# Nakuja_esp_lora_gps_sd.net
KiCad netlist of a schematic drawn in EasyEDA
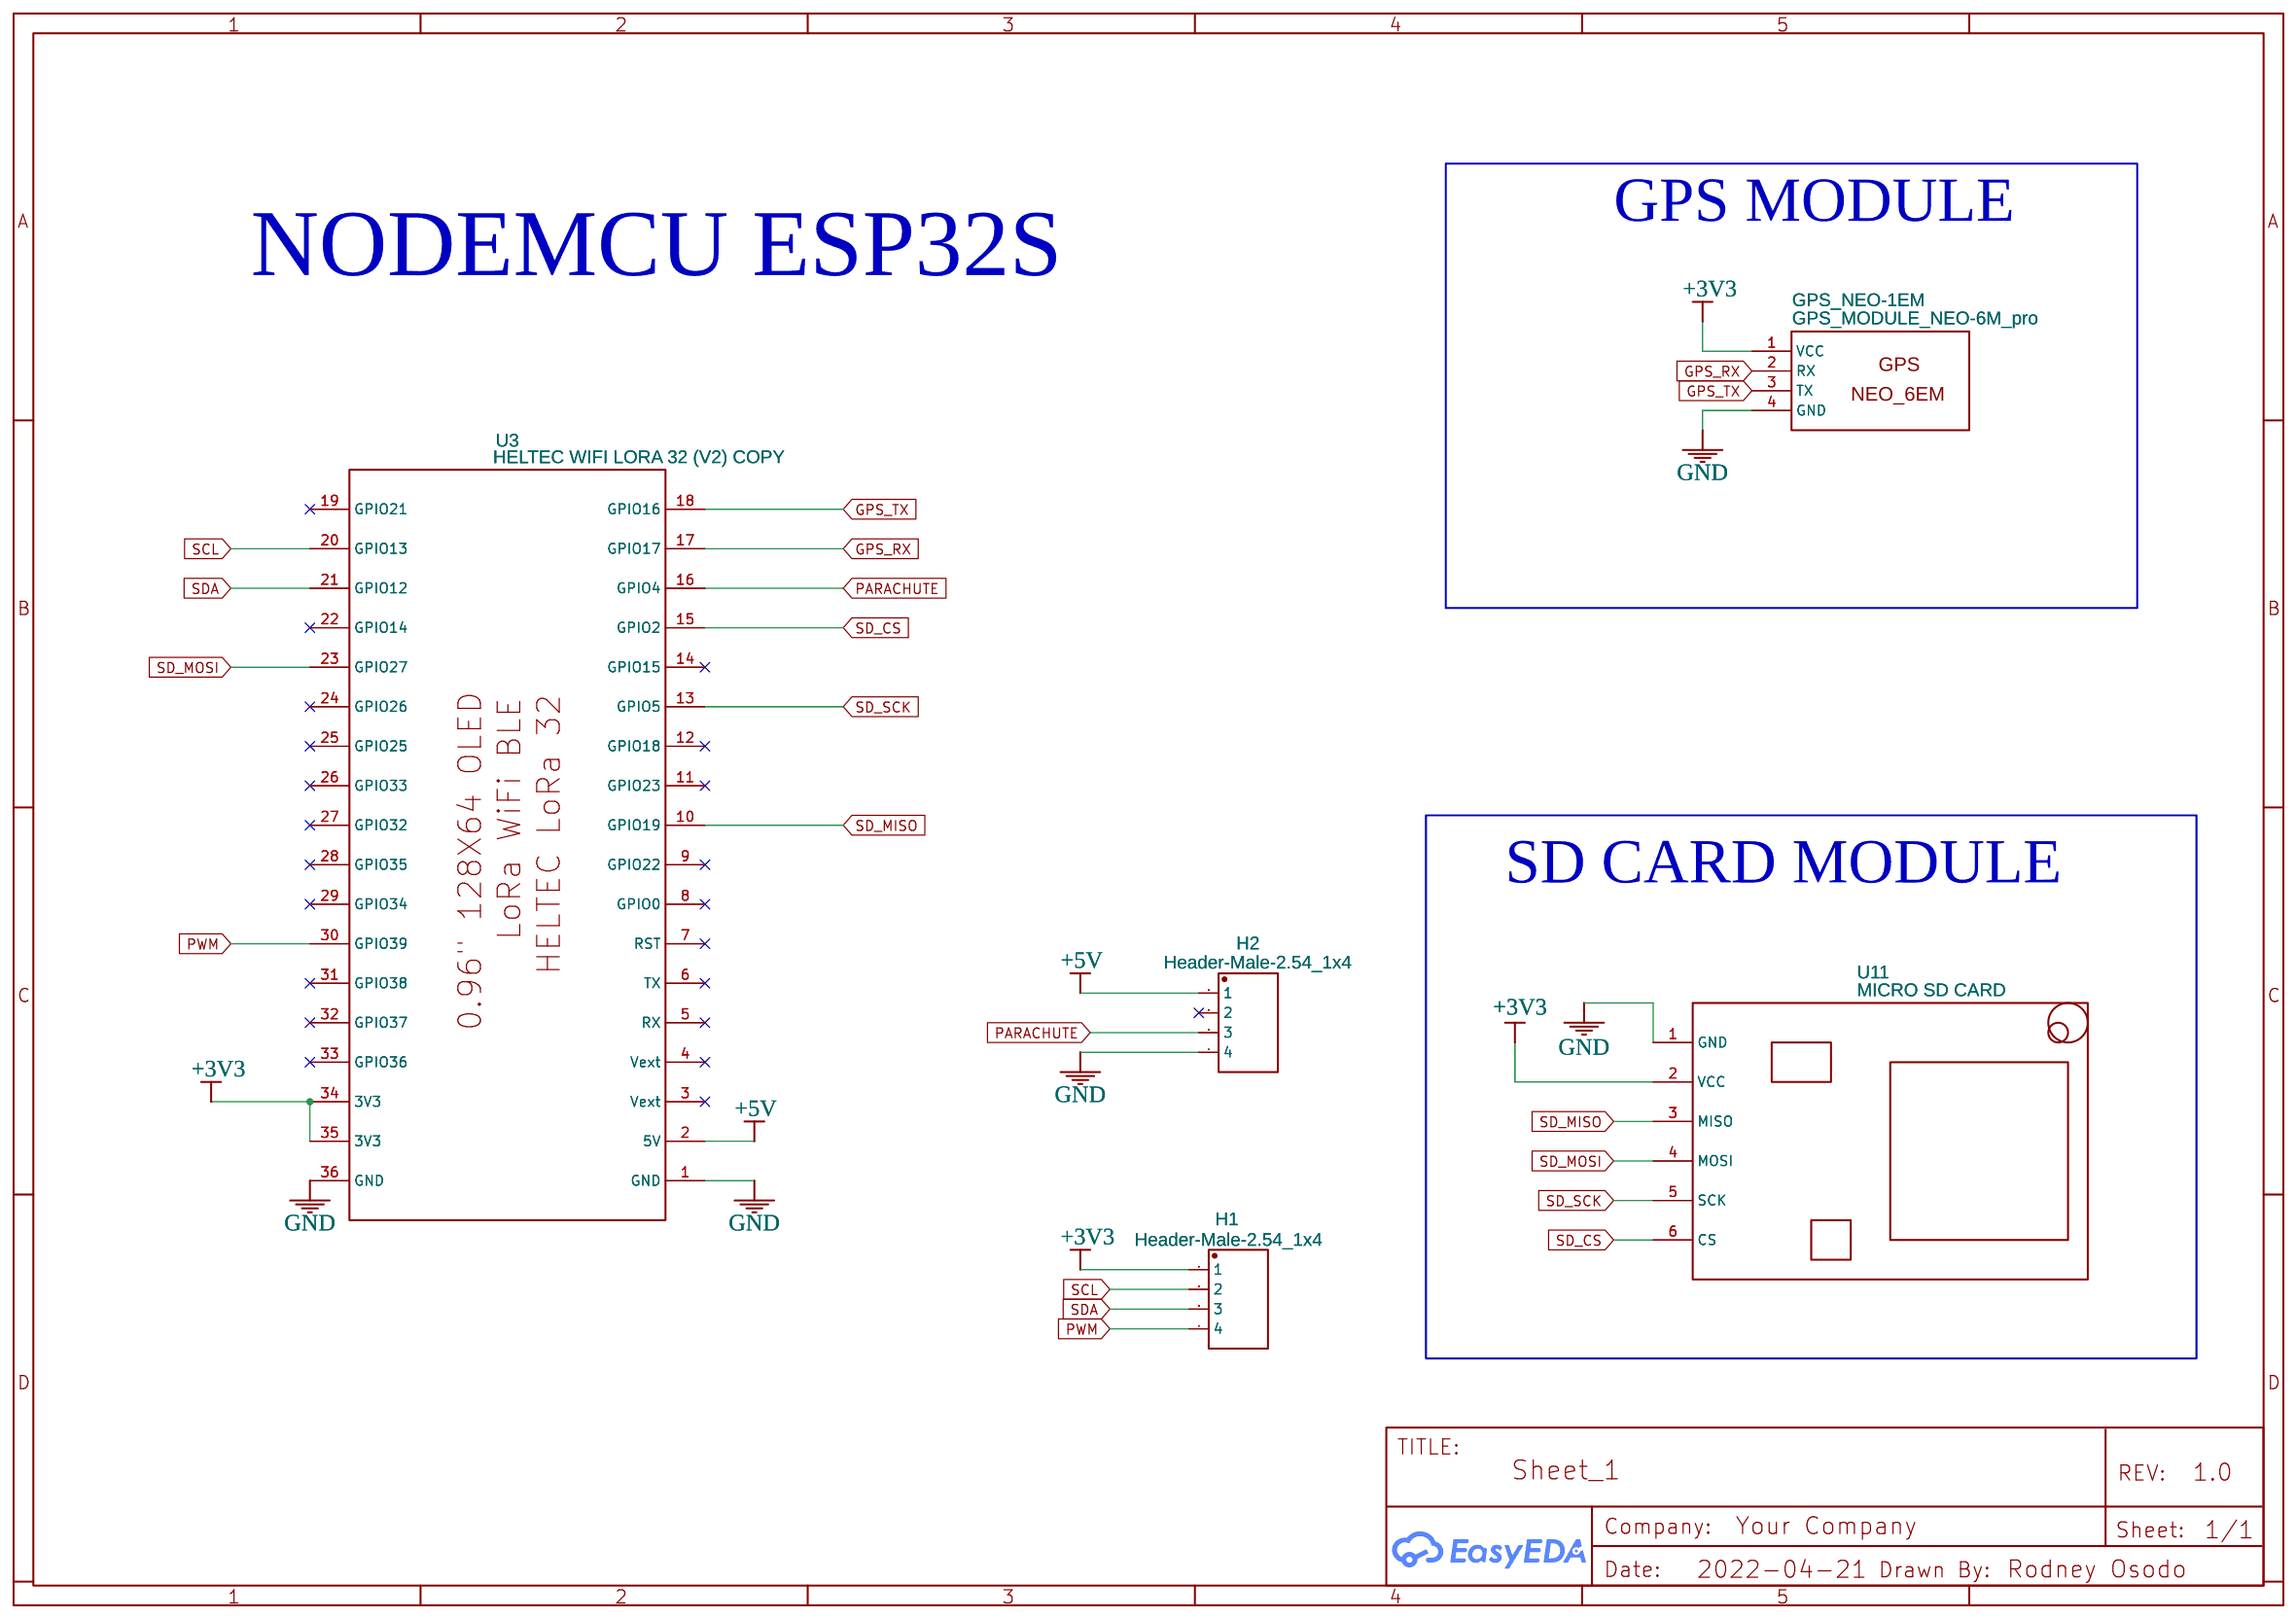
[diagram p0: schematic sheet]

(export (version "E")
  (design (tool "Eeschema 10.0.6"))
  (components
    (comp (ref "GPS_NEO-1EM")
      (value "GPS_MODULE_NEO-6M_pro")
      (libsource (lib "") (part "GPS_MODULE_NEO-6M_pro"))
    )
    (comp (ref "H1")
      (value "Header-Male-2.54_1x4")
      (fields
        (field (name "BOM_Manufacturer Part") "210S-1*4P L=11.6MMGold-plated black")
        (field (name "BOM_Supplier Part") "C124378")
      )
      (libsource (lib "") (part "Header-Male-2.54_1x4"))
    )
    (comp (ref "H2")
      (value "Header-Male-2.54_1x4")
      (fields
        (field (name "BOM_Manufacturer Part") "210S-1*4P L=11.6MMGold-plated black")
        (field (name "BOM_Supplier Part") "C124378")
      )
      (libsource (lib "") (part "Header-Male-2.54_1x4"))
    )
    (comp (ref "U3")
      (value "HELTEC WIFI LORA 32 (V2) COPY")
      (fields (field (name "BOM_Manufacturer Part") "Heltec WiFi LoRa 32(V2)"))
      (libsource (lib "") (part "HELTEC WIFI LORA 32 (V2) COPY"))
    )
    (comp (ref "U11") (value "MICRO SD CARD") (libsource (lib "") (part "MICRO SD CARD")))
  )
  (nets
    (net (code "1") (name "+3V3") (class "Default")
      (node (ref "GPS_NEO-1EM") (pin "1") (pinfunction "VCC_1") (pintype "passive"))
      (node (ref "H1") (pin "1") (pinfunction "1_1") (pintype "unspecified"))
      (node (ref "U11") (pin "2") (pinfunction "VCC_2") (pintype "unspecified"))
      (node (ref "U3") (pin "34") (pinfunction "3V3_34") (pintype "unspecified"))
      (node (ref "U3") (pin "35") (pinfunction "3V3_35") (pintype "unspecified"))
    )
    (net (code "2") (name "+5V") (class "Default")
      (node (ref "H2") (pin "1") (pinfunction "1_1") (pintype "unspecified"))
      (node (ref "U3") (pin "2") (pinfunction "5V_2") (pintype "unspecified"))
    )
    (net (code "3") (name "GND") (class "Default")
      (node (ref "GPS_NEO-1EM") (pin "4") (pinfunction "GND_4") (pintype "passive"))
      (node (ref "H2") (pin "4") (pinfunction "4_4") (pintype "unspecified"))
      (node (ref "U11") (pin "1") (pinfunction "GND_1") (pintype "unspecified"))
      (node (ref "U3") (pin "1") (pinfunction "GND_1") (pintype "unspecified"))
      (node (ref "U3") (pin "36") (pinfunction "GND_36") (pintype "unspecified"))
    )
    (net (code "4") (name "GPS_RX") (class "Default")
      (node (ref "GPS_NEO-1EM") (pin "2") (pinfunction "RX_2") (pintype "input"))
      (node (ref "U3") (pin "17") (pinfunction "GPIO17_17") (pintype "unspecified"))
    )
    (net (code "5") (name "GPS_TX") (class "Default")
      (node (ref "GPS_NEO-1EM") (pin "3") (pinfunction "TX_3") (pintype "output"))
      (node (ref "U3") (pin "18") (pinfunction "GPIO16_18") (pintype "unspecified"))
    )
    (net (code "6") (name "PARACHUTE") (class "Default")
      (node (ref "H2") (pin "3") (pinfunction "3_3") (pintype "unspecified"))
      (node (ref "U3") (pin "16") (pinfunction "GPIO4_16") (pintype "unspecified"))
    )
    (net (code "7") (name "PWM") (class "Default")
      (node (ref "H1") (pin "4") (pinfunction "4_4") (pintype "unspecified"))
      (node (ref "U3") (pin "30") (pinfunction "GPIO39_30") (pintype "unspecified"))
    )
    (net (code "8") (name "SCL") (class "Default")
      (node (ref "H1") (pin "2") (pinfunction "2_2") (pintype "unspecified"))
      (node (ref "U3") (pin "20") (pinfunction "GPIO13_20") (pintype "unspecified"))
    )
    (net (code "9") (name "SDA") (class "Default")
      (node (ref "H1") (pin "3") (pinfunction "3_3") (pintype "unspecified"))
      (node (ref "U3") (pin "21") (pinfunction "GPIO12_21") (pintype "unspecified"))
    )
    (net (code "10") (name "SD_CS") (class "Default")
      (node (ref "U11") (pin "6") (pinfunction "CS_6") (pintype "unspecified"))
      (node (ref "U3") (pin "15") (pinfunction "GPIO2_15") (pintype "unspecified"))
    )
    (net (code "11") (name "SD_MISO") (class "Default")
      (node (ref "U11") (pin "3") (pinfunction "MISO_3") (pintype "unspecified"))
      (node (ref "U3") (pin "10") (pinfunction "GPIO19_10") (pintype "unspecified"))
    )
    (net (code "12") (name "SD_MOSI") (class "Default")
      (node (ref "U11") (pin "4") (pinfunction "MOSI_4") (pintype "unspecified"))
      (node (ref "U3") (pin "23") (pinfunction "GPIO27_23") (pintype "unspecified"))
    )
    (net (code "13") (name "SD_SCK") (class "Default")
      (node (ref "U11") (pin "5") (pinfunction "SCK_5") (pintype "unspecified"))
      (node (ref "U3") (pin "13") (pinfunction "GPIO5_13") (pintype "unspecified"))
    )
    (net (code "14") (name "unconnected-(H2-Pad2)") (class "Default")
      (node (ref "H2") (pin "2") (pinfunction "2_2") (pintype "unspecified+no_connect"))
    )
    (net (code "15") (name "unconnected-(U3-GPIO0-Pad8)") (class "Default")
      (node (ref "U3") (pin "8") (pinfunction "GPIO0_8") (pintype "unspecified+no_connect"))
    )
    (net (code "16") (name "unconnected-(U3-GPIO14-Pad22)") (class "Default")
      (node (ref "U3") (pin "22") (pinfunction "GPIO14_22") (pintype "unspecified+no_connect"))
    )
    (net (code "17") (name "unconnected-(U3-GPIO15-Pad14)") (class "Default")
      (node (ref "U3") (pin "14") (pinfunction "GPIO15_14") (pintype "unspecified+no_connect"))
    )
    (net (code "18") (name "unconnected-(U3-GPIO18-Pad12)") (class "Default")
      (node (ref "U3") (pin "12") (pinfunction "GPIO18_12") (pintype "unspecified+no_connect"))
    )
    (net (code "19") (name "unconnected-(U3-GPIO21-Pad19)") (class "Default")
      (node (ref "U3") (pin "19") (pinfunction "GPIO21_19") (pintype "unspecified+no_connect"))
    )
    (net (code "20") (name "unconnected-(U3-GPIO22-Pad9)") (class "Default")
      (node (ref "U3") (pin "9") (pinfunction "GPIO22_9") (pintype "unspecified+no_connect"))
    )
    (net (code "21") (name "unconnected-(U3-GPIO23-Pad11)") (class "Default")
      (node (ref "U3") (pin "11") (pinfunction "GPIO23_11") (pintype "unspecified+no_connect"))
    )
    (net (code "22") (name "unconnected-(U3-GPIO25-Pad25)") (class "Default")
      (node (ref "U3") (pin "25") (pinfunction "GPIO25_25") (pintype "unspecified+no_connect"))
    )
    (net (code "23") (name "unconnected-(U3-GPIO26-Pad24)") (class "Default")
      (node (ref "U3") (pin "24") (pinfunction "GPIO26_24") (pintype "unspecified+no_connect"))
    )
    (net (code "24") (name "unconnected-(U3-GPIO32-Pad27)") (class "Default")
      (node (ref "U3") (pin "27") (pinfunction "GPIO32_27") (pintype "unspecified+no_connect"))
    )
    (net (code "25") (name "unconnected-(U3-GPIO33-Pad26)") (class "Default")
      (node (ref "U3") (pin "26") (pinfunction "GPIO33_26") (pintype "unspecified+no_connect"))
    )
    (net (code "26") (name "unconnected-(U3-GPIO34-Pad29)") (class "Default")
      (node (ref "U3") (pin "29") (pinfunction "GPIO34_29") (pintype "unspecified+no_connect"))
    )
    (net (code "27") (name "unconnected-(U3-GPIO35-Pad28)") (class "Default")
      (node (ref "U3") (pin "28") (pinfunction "GPIO35_28") (pintype "unspecified+no_connect"))
    )
    (net (code "28") (name "unconnected-(U3-GPIO36-Pad33)") (class "Default")
      (node (ref "U3") (pin "33") (pinfunction "GPIO36_33") (pintype "unspecified+no_connect"))
    )
    (net (code "29") (name "unconnected-(U3-GPIO37-Pad32)") (class "Default")
      (node (ref "U3") (pin "32") (pinfunction "GPIO37_32") (pintype "unspecified+no_connect"))
    )
    (net (code "30") (name "unconnected-(U3-GPIO38-Pad31)") (class "Default")
      (node (ref "U3") (pin "31") (pinfunction "GPIO38_31") (pintype "unspecified+no_connect"))
    )
    (net (code "31") (name "unconnected-(U3-RST-Pad7)") (class "Default")
      (node (ref "U3") (pin "7") (pinfunction "RST_7") (pintype "unspecified+no_connect"))
    )
    (net (code "32") (name "unconnected-(U3-RX-Pad5)") (class "Default")
      (node (ref "U3") (pin "5") (pinfunction "RX_5") (pintype "unspecified+no_connect"))
    )
    (net (code "33") (name "unconnected-(U3-TX-Pad6)") (class "Default")
      (node (ref "U3") (pin "6") (pinfunction "TX_6") (pintype "unspecified+no_connect"))
    )
    (net (code "34") (name "unconnected-(U3-Vext-Pad3)") (class "Default")
      (node (ref "U3") (pin "3") (pinfunction "Vext_3") (pintype "unspecified+no_connect"))
    )
    (net (code "35") (name "unconnected-(U3-Vext-Pad4)") (class "Default")
      (node (ref "U3") (pin "4") (pinfunction "Vext_4") (pintype "unspecified+no_connect"))
    )
  )
)
